# usb_switch.net
KiCad netlist of a schematic drawn in EAGLE
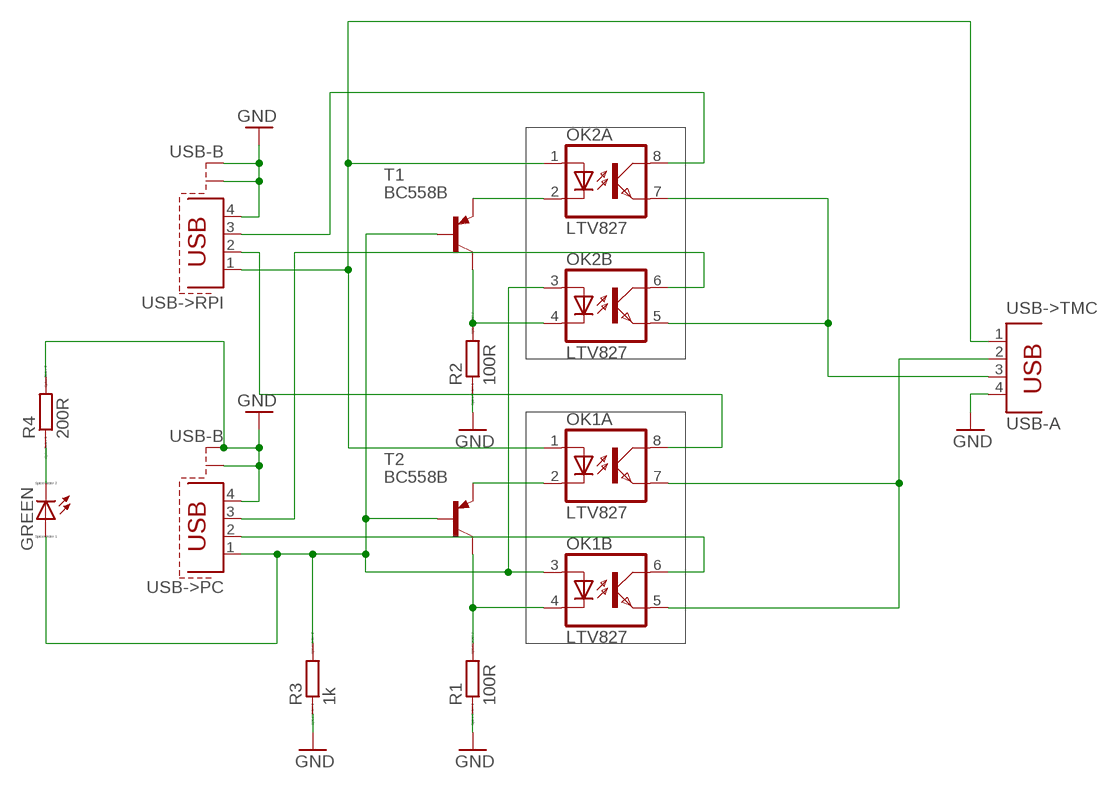
[diagram p0: schematic, sheet 1]

(export (version "E")
  (design (tool "Eeschema 10.0.6"))
  (components
    (comp (ref "GREEN")
      (value "LED_ELD260")
      (footprint "eagle-import:LED_LD260")
      (libsource (lib "eagle-import") (part "LED_ELD260"))
    )
    (comp (ref "OK1")
      (value "LTV827")
      (footprint "eagle-import:DIL08")
      (libsource (lib "eagle-import") (part "LTV826"))
    )
    (comp (ref "OK2")
      (value "LTV827")
      (footprint "eagle-import:DIL08")
      (libsource (lib "eagle-import") (part "LTV826"))
    )
    (comp (ref "R1")
      (value "100R")
      (footprint "eagle-import:0204_7")
      (libsource (lib "eagle-import") (part "R0204/7"))
    )
    (comp (ref "R2")
      (value "100R")
      (footprint "eagle-import:0204_7")
      (libsource (lib "eagle-import") (part "R0204/7"))
    )
    (comp (ref "R3")
      (value "1k")
      (footprint "eagle-import:0204_7")
      (libsource (lib "eagle-import") (part "R0204/7"))
    )
    (comp (ref "R4")
      (value "200R")
      (footprint "eagle-import:0204_7")
      (libsource (lib "eagle-import") (part "R0204/7"))
    )
    (comp (ref "T1")
      (value "BC558B")
      (footprint "eagle-import:TO92-BEC")
      (libsource (lib "eagle-import") (part "-PNP-TO92-BEC"))
    )
    (comp (ref "T2")
      (value "BC558B")
      (footprint "eagle-import:TO92-BEC")
      (libsource (lib "eagle-import") (part "-PNP-TO92-BEC"))
    )
    (comp (ref "USB->PC")
      (value "USB-B")
      (footprint "eagle-import:PN61729-S")
      (libsource (lib "eagle-import") (part "PN61729-S"))
    )
    (comp (ref "USB->RPI")
      (value "USB-B")
      (footprint "eagle-import:PN61729-S")
      (libsource (lib "eagle-import") (part "PN61729-S"))
    )
    (comp (ref "USB->TMC")
      (value "USB-A")
      (footprint "eagle-import:PN87520")
      (libsource (lib "eagle-import") (part "PN87520"))
    )
  )
  (nets
    (net (code "1") (name "GND") (class "Default")
      (node (ref "R1") (pin "1") (pinfunction "1_1") (pintype "passive"))
      (node (ref "R2") (pin "1") (pinfunction "1_1") (pintype "passive"))
      (node (ref "R3") (pin "1") (pinfunction "1_1") (pintype "passive"))
      (node (ref "R4") (pin "2") (pinfunction "2_2") (pintype "passive"))
      (node (ref "USB->PC") (pin "4") (pinfunction "4_4") (pintype "passive"))
      (node (ref "USB->PC") (pin "S1") (pinfunction "S1_S1") (pintype "passive"))
      (node (ref "USB->PC") (pin "S2") (pinfunction "S2_S2") (pintype "passive"))
      (node (ref "USB->RPI") (pin "4") (pinfunction "4_4") (pintype "passive"))
      (node (ref "USB->RPI") (pin "S1") (pinfunction "S1_S1") (pintype "passive"))
      (node (ref "USB->RPI") (pin "S2") (pinfunction "S2_S2") (pintype "passive"))
      (node (ref "USB->TMC") (pin "4") (pinfunction "4_4") (pintype "passive"))
    )
    (net (code "2") (name "Net-(GREEN-C)") (class "Default")
      (node (ref "GREEN") (pin "K") (pinfunction "C_K") (pintype "passive"))
      (node (ref "R4") (pin "1") (pinfunction "1_1") (pintype "passive"))
    )
    (net (code "3") (name "Net-(OK1A-A)") (class "Default")
      (node (ref "OK1") (pin "1") (pinfunction "A_1") (pintype "passive"))
      (node (ref "OK2") (pin "1") (pinfunction "A_1") (pintype "passive"))
      (node (ref "USB->RPI") (pin "1") (pinfunction "1_1") (pintype "passive"))
      (node (ref "USB->TMC") (pin "1") (pinfunction "1_1") (pintype "passive"))
    )
    (net (code "4") (name "Net-(OK1A-C)") (class "Default")
      (node (ref "OK1") (pin "2") (pinfunction "C_2") (pintype "passive"))
      (node (ref "T2") (pin "E") (pinfunction "E_E") (pintype "passive"))
    )
    (net (code "5") (name "Net-(OK1A-COL)") (class "Default")
      (node (ref "OK1") (pin "8") (pinfunction "COL_8") (pintype "passive"))
      (node (ref "USB->RPI") (pin "2") (pinfunction "2_2") (pintype "passive"))
    )
    (net (code "6") (name "Net-(OK1A-EMIT)") (class "Default")
      (node (ref "OK1") (pin "5") (pinfunction "EMIT_5") (pintype "passive"))
      (node (ref "OK1") (pin "7") (pinfunction "EMIT_7") (pintype "passive"))
      (node (ref "USB->TMC") (pin "2") (pinfunction "2_2") (pintype "passive"))
    )
    (net (code "7") (name "Net-(OK1B-A)") (class "Default")
      (node (ref "GREEN") (pin "A") (pinfunction "A_A") (pintype "passive"))
      (node (ref "OK1") (pin "3") (pinfunction "A_3") (pintype "passive"))
      (node (ref "OK2") (pin "3") (pinfunction "A_3") (pintype "passive"))
      (node (ref "R3") (pin "2") (pinfunction "2_2") (pintype "passive"))
      (node (ref "T1") (pin "B") (pinfunction "B_B") (pintype "passive"))
      (node (ref "T2") (pin "B") (pinfunction "B_B") (pintype "passive"))
      (node (ref "USB->PC") (pin "1") (pinfunction "1_1") (pintype "passive"))
    )
    (net (code "8") (name "Net-(OK1B-C)") (class "Default")
      (node (ref "OK1") (pin "4") (pinfunction "C_4") (pintype "passive"))
      (node (ref "R1") (pin "2") (pinfunction "2_2") (pintype "passive"))
      (node (ref "T2") (pin "C") (pinfunction "C_C") (pintype "passive"))
    )
    (net (code "9") (name "Net-(OK1B-COL)") (class "Default")
      (node (ref "OK1") (pin "6") (pinfunction "COL_6") (pintype "passive"))
      (node (ref "USB->PC") (pin "2") (pinfunction "2_2") (pintype "passive"))
    )
    (net (code "10") (name "Net-(OK2A-C)") (class "Default")
      (node (ref "OK2") (pin "2") (pinfunction "C_2") (pintype "passive"))
      (node (ref "T1") (pin "E") (pinfunction "E_E") (pintype "passive"))
    )
    (net (code "11") (name "Net-(OK2A-COL)") (class "Default")
      (node (ref "OK2") (pin "8") (pinfunction "COL_8") (pintype "passive"))
      (node (ref "USB->RPI") (pin "3") (pinfunction "3_3") (pintype "passive"))
    )
    (net (code "12") (name "Net-(OK2A-EMIT)") (class "Default")
      (node (ref "OK2") (pin "5") (pinfunction "EMIT_5") (pintype "passive"))
      (node (ref "OK2") (pin "7") (pinfunction "EMIT_7") (pintype "passive"))
      (node (ref "USB->TMC") (pin "3") (pinfunction "3_3") (pintype "passive"))
    )
    (net (code "13") (name "Net-(OK2B-C)") (class "Default")
      (node (ref "OK2") (pin "4") (pinfunction "C_4") (pintype "passive"))
      (node (ref "R2") (pin "2") (pinfunction "2_2") (pintype "passive"))
      (node (ref "T1") (pin "C") (pinfunction "C_C") (pintype "passive"))
    )
    (net (code "14") (name "Net-(OK2B-COL)") (class "Default")
      (node (ref "OK2") (pin "6") (pinfunction "COL_6") (pintype "passive"))
      (node (ref "USB->PC") (pin "3") (pinfunction "3_3") (pintype "passive"))
    )
  )
)
